# CAN_IF.net
KiCad netlist of a schematic drawn in Altium Designer
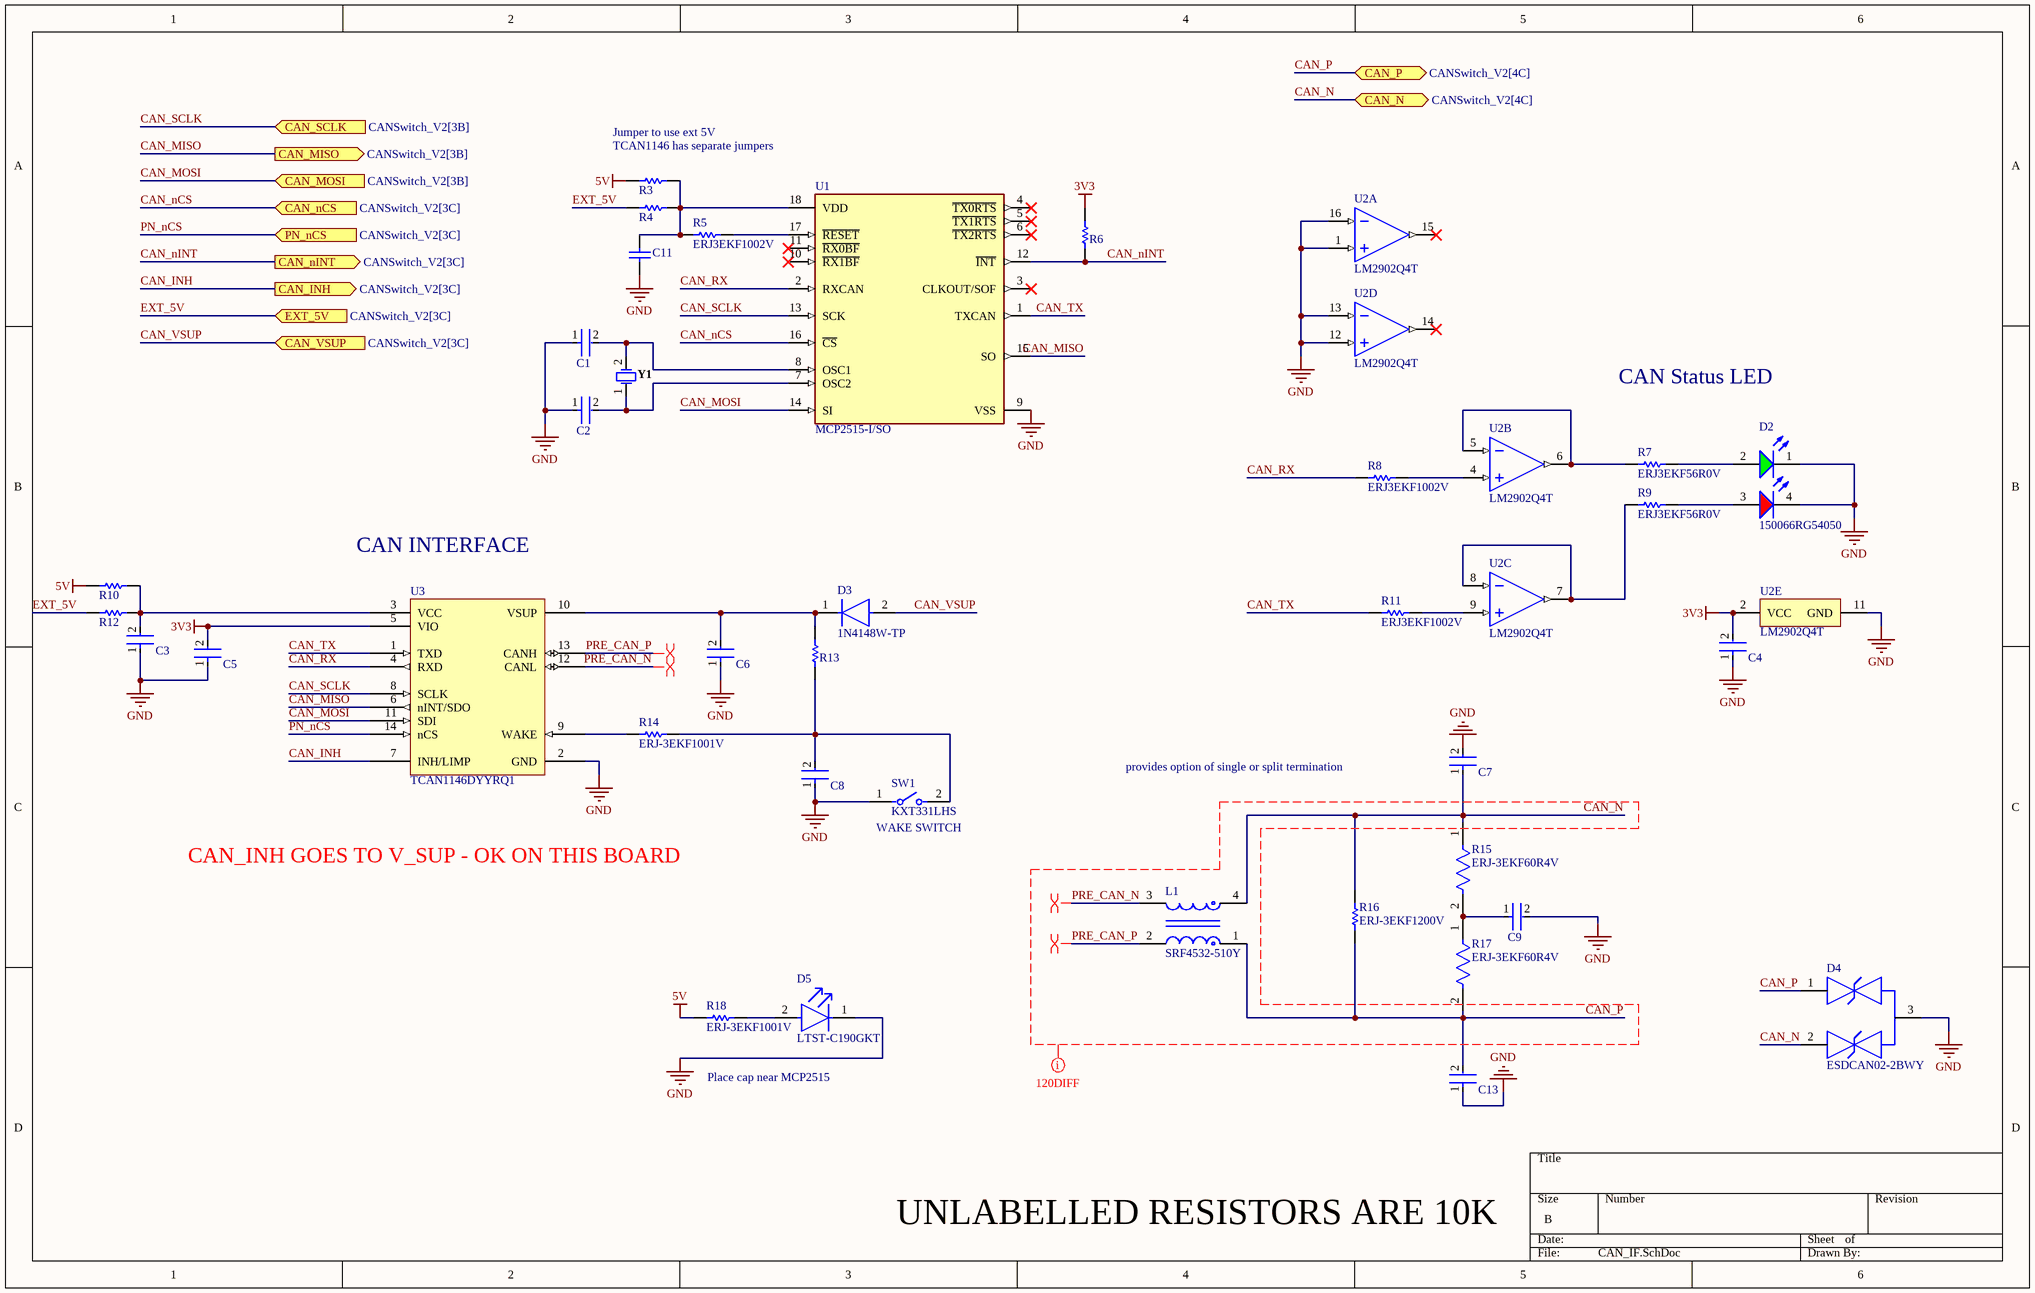
[diagram p0: CAN_IF.SchDoc]

(export (version "E")
  (design (tool "Eeschema 10.0.6"))
  (components
    (comp (ref "C1")
      (value "GRM188R60J106ME47D")
      (footprint "FP-GRM188-0_1-e0_2_0_55-IPC_A")
      (description "Chip Multilayer Ceramic Capacitors for General Purpose, 0603, 10uF, X5R, 15%, 20%, 6.3V")
      (fields (field (name "VOLTAGE") "6.3V") (field (name "TOLERANCE") "20%"))
      (libsource (lib "Altium Content Vault") (part "02cd4be3c70576c341d710602a673aa"))
    )
    (comp (ref "C2")
      (value "GRM188R60J106ME47D")
      (footprint "FP-GRM188-0_1-e0_2_0_55-IPC_A")
      (description "Chip Multilayer Ceramic Capacitors for General Purpose, 0603, 10uF, X5R, 15%, 20%, 6.3V")
      (fields (field (name "VOLTAGE") "6.3V") (field (name "TOLERANCE") "20%"))
      (libsource (lib "Altium Content Vault") (part "02cd4be3c70576c341d710602a673aa"))
    )
    (comp (ref "C3")
      (value "C0402C104K8PACTU")
      (footprint "FP-C0402-BB-MFG")
      (description "CAP CER 0.1UF 10V X5R 0402")
      (fields (field (name "MANUFACTURER") "Kemet") (field (name "TOLERANCE") "0.1"))
      (libsource (lib "Altium Content Vault") (part "b4654b650e69147ec39a6b967a45e02"))
    )
    (comp (ref "C4")
      (value "C0402C104K8PACTU")
      (footprint "FP-C0402-BB-MFG")
      (description "CAP CER 0.1UF 10V X5R 0402")
      (fields (field (name "MANUFACTURER") "Kemet") (field (name "TOLERANCE") "0.1"))
      (libsource (lib "Altium Content Vault") (part "b4654b650e69147ec39a6b967a45e02"))
    )
    (comp (ref "C5")
      (value "C0402C104K8PACTU")
      (footprint "FP-C0402-BB-MFG")
      (description "CAP CER 0.1UF 10V X5R 0402")
      (fields (field (name "MANUFACTURER") "Kemet") (field (name "TOLERANCE") "0.1"))
      (libsource (lib "Altium Content Vault") (part "b4654b650e69147ec39a6b967a45e02"))
    )
    (comp (ref "C6")
      (value "C0402C104K8PACTU")
      (footprint "FP-C0402-BB-MFG")
      (description "CAP CER 0.1UF 10V X5R 0402")
      (fields (field (name "MANUFACTURER") "Kemet") (field (name "TOLERANCE") "0.1"))
      (libsource (lib "Altium Content Vault") (part "b4654b650e69147ec39a6b967a45e02"))
    )
    (comp (ref "C7")
      (value "C0402C104K8PACTU")
      (footprint "FP-C0402-BB-MFG")
      (description "CAP CER 0.1UF 10V X5R 0402")
      (fields (field (name "MANUFACTURER") "Kemet") (field (name "TOLERANCE") "0.1"))
      (libsource (lib "Altium Content Vault") (part "b4654b650e69147ec39a6b967a45e02"))
    )
    (comp (ref "C8")
      (value "C0402C104K8PACTU")
      (footprint "FP-C0402-BB-MFG")
      (description "CAP CER 0.1UF 10V X5R 0402")
      (fields (field (name "MANUFACTURER") "Kemet") (field (name "TOLERANCE") "0.1"))
      (libsource (lib "Altium Content Vault") (part "b4654b650e69147ec39a6b967a45e02"))
    )
    (comp (ref "C9")
      (value "C0402C104K8PACTU")
      (footprint "FP-C0402-BB-MFG")
      (description "CAP CER 0.1UF 10V X5R 0402")
      (fields (field (name "MANUFACTURER") "Kemet") (field (name "TOLERANCE") "0.1"))
      (libsource (lib "Altium Content Vault") (part "b4654b650e69147ec39a6b967a45e02"))
    )
    (comp (ref "C11")
      (value "1206GC102KAT1A")
      (footprint "AVX-1206-2_L")
      (description "Chip Capacitor, 1 nF, +/- 10%, -55 to 125 degC, 1206 (3216 Metric), RoHS, Tape and Reel")
      (fields (field (name "TOLERANCE") "10%") (field (name "MANUFACTURER") "AVX"))
      (libsource (lib "Altium Content Vault") (part "CAP-NP-2"))
    )
    (comp (ref "C13")
      (value "C0402C104K8PACTU")
      (footprint "FP-C0402-BB-MFG")
      (description "CAP CER 0.1UF 10V X5R 0402")
      (fields (field (name "MANUFACTURER") "Kemet") (field (name "TOLERANCE") "0.1"))
      (libsource (lib "Altium Content Vault") (part "b4654b650e69147ec39a6b967a45e02"))
    )
    (comp (ref "D2")
      (value "150066RG54050")
      (footprint "WL-SBCD_0606")
      (description "Led, Red/Grn, 180Mcd/230Mcd, 624Nm/525Nm Rohs Compliant: Yes")
      (libsource (lib "uORocketry Hardware") (part "WL-SBCD_0606_Red & Green"))
    )
    (comp (ref "D3")
      (value "1N4148W-TP")
      (footprint "FP-SOD-123-IPC_A")
      (description "DIODE GEN PURP 100V 150MA SOD123")
      (libsource (lib "Altium Content Vault") (part "d7152d700b627762746794eb795d46e"))
    )
    (comp (ref "D4")
      (value "ESDCAN02-2BWY")
      (footprint "FP-SOT323-3L-MFG")
      (description "TVS DIODE 26.5V 44V SOT323-3")
      (fields
        (field (name "MANUFACTURER") "STMicroelectronics")
        (field (name "OCTOPART") "https://octopart.com/esdcan02-2bwy-stmicroelectronics-58631133")
      )
      (libsource (lib "Altium Content Vault") (part "0b9019fb5e52ed66df21ec1535be59d"))
    )
    (comp (ref "D5")
      (value "LTST-C190GKT")
      (footprint "FP-LTST-C190GKT-MFG")
      (description "LED GREEN CLEAR CHIP SMD")
      (fields (field (name "VOLTAGE") "2V"))
      (libsource (lib "Altium Content Vault") (part "8706943c75ba83719d021d2fdc84c58"))
    )
    (comp (ref "L1")
      (value "SRF4532-510Y")
      (footprint "FP-SRF4532-MFG")
      (description "CMC 51UH 200MA 2LN 2KOHM SMD")
      (fields (field (name "TOLERANCE") "50%"))
      (libsource (lib "Altium Content Vault") (part "aca3f6a10b859f211cca95010157f3b"))
    )
    (comp (ref "R3")
      (value "0402 JUMPER 0 OHM")
      (footprint "RESC1005X40X25NL05T05")
      (description "READ THE NAME")
      (libsource (lib "uORocketry Hardware") (part "RES"))
    )
    (comp (ref "R4")
      (value "0402 JUMPER 0 OHM")
      (footprint "RESC1005X40X25NL05T05")
      (description "READ THE NAME")
      (libsource (lib "uORocketry Hardware") (part "RES"))
    )
    (comp (ref "R5")
      (value "ERJ3EKF1002V")
      (footprint "RESC1609X55X30LL15T15")
      (description "Chip Resistor, 10 KOhm, +/- 1%, 0.1 W, -55 to 155 degC, 0603 (1608 Metric), RoHS, Tape and Reel")
      (fields (field (name "TOLERANCE") "1%") (field (name "MANUFACTURER") "Panasonic"))
      (libsource (lib "Altium Content Vault") (part "RES-2"))
    )
    (comp (ref "R6")
      (value "ERJ3EKF1002V")
      (footprint "RESC1609X55X30LL15T15")
      (description "Chip Resistor, 10 KOhm, +/- 1%, 0.1 W, -55 to 155 degC, 0603 (1608 Metric), RoHS, Tape and Reel")
      (fields (field (name "TOLERANCE") "1%") (field (name "MANUFACTURER") "Panasonic"))
      (libsource (lib "Altium Content Vault") (part "RES-2"))
    )
    (comp (ref "R7")
      (value "ERJ3EKF56R0V")
      (footprint "RESC1608X55X30NL15T15")
      (fields (field (name "MANUFACTURER") "Panasonic"))
      (libsource (lib "Altium Content Vault") (part "RES"))
    )
    (comp (ref "R8")
      (value "ERJ3EKF1002V")
      (footprint "RESC1609X55X30LL15T15")
      (description "Chip Resistor, 10 KOhm, +/- 1%, 0.1 W, -55 to 155 degC, 0603 (1608 Metric), RoHS, Tape and Reel")
      (fields (field (name "TOLERANCE") "1%") (field (name "MANUFACTURER") "Panasonic"))
      (libsource (lib "Altium Content Vault") (part "RES-2"))
    )
    (comp (ref "R9")
      (value "ERJ3EKF56R0V")
      (footprint "RESC1608X55X30NL15T15")
      (fields (field (name "MANUFACTURER") "Panasonic"))
      (libsource (lib "Altium Content Vault") (part "RES"))
    )
    (comp (ref "R10")
      (value "0402 JUMPER 0 OHM")
      (footprint "RESC1005X40X25NL05T05")
      (description "READ THE NAME")
      (libsource (lib "uORocketry Hardware") (part "RES"))
    )
    (comp (ref "R11")
      (value "ERJ3EKF1002V")
      (footprint "RESC1609X55X30LL15T15")
      (description "Chip Resistor, 10 KOhm, +/- 1%, 0.1 W, -55 to 155 degC, 0603 (1608 Metric), RoHS, Tape and Reel")
      (fields (field (name "TOLERANCE") "1%") (field (name "MANUFACTURER") "Panasonic"))
      (libsource (lib "Altium Content Vault") (part "RES-2"))
    )
    (comp (ref "R12")
      (value "0402 JUMPER 0 OHM")
      (footprint "RESC1005X40X25NL05T05")
      (description "READ THE NAME")
      (libsource (lib "uORocketry Hardware") (part "RES"))
    )
    (comp (ref "R13")
      (value "ERJ3EKF1002V")
      (footprint "RESC1609X55X30LL15T15")
      (description "Chip Resistor, 10 KOhm, +/- 1%, 0.1 W, -55 to 155 degC, 0603 (1608 Metric), RoHS, Tape and Reel")
      (fields (field (name "TOLERANCE") "1%") (field (name "MANUFACTURER") "Panasonic"))
      (libsource (lib "Altium Content Vault") (part "RES-2"))
    )
    (comp (ref "R14")
      (value "ERJ-3EKF1001V")
      (footprint "RESC1608X55X30LL15T15")
      (fields (field (name "MANUFACTURER") "Panasonic"))
      (libsource (lib "Altium Content Vault") (part "RES"))
    )
    (comp (ref "R15")
      (value "ERJ-3EKF60R4V")
      (footprint "FP-ERJ3EK-IPC_C")
      (description "RES SMD 60.4 OHM 1% 1/10W 0603")
      (fields (field (name "TOLERANCE") "1%"))
      (libsource (lib "Altium Content Vault") (part "1029c3af85768c4190bb7ad29bc67b5"))
    )
    (comp (ref "R16")
      (value "ERJ-3EKF1200V")
      (footprint "RESC1609X55X30ML15T15")
      (description "Chip Resistor, 120 Ohm, +/- 1%, 0.1 W, -55 to 155 degC, 0603 (1608 Metric), RoHS, Tape and Reel")
      (fields (field (name "TOLERANCE") "1%") (field (name "MANUFACTURER") "Panasonic"))
      (libsource (lib "Altium Content Vault") (part "RES-2"))
    )
    (comp (ref "R17")
      (value "ERJ-3EKF60R4V")
      (footprint "FP-ERJ3EK-IPC_C")
      (description "RES SMD 60.4 OHM 1% 1/10W 0603")
      (fields (field (name "TOLERANCE") "1%"))
      (libsource (lib "Altium Content Vault") (part "1029c3af85768c4190bb7ad29bc67b5"))
    )
    (comp (ref "R18")
      (value "ERJ-3EKF1001V")
      (footprint "RESC1608X55X30LL15T15")
      (fields (field (name "MANUFACTURER") "Panasonic"))
      (libsource (lib "Altium Content Vault") (part "RES"))
    )
    (comp (ref "SW1")
      (value "KXT331LHS")
      (footprint "FP-KXT331LHS-MFG")
      (description "SWITCH TACTILE SPST-NO 0.02A 15V")
      (libsource (lib "Altium Content Vault") (part "bb27bde45df87f1f469753f287ef5ae"))
    )
    (comp (ref "U1")
      (value "MCP2515-I/SO")
      (footprint "FP-C04-051-MFG")
      (description "IC CAN CONTROLLER W/SPI 18SOIC")
      (fields
        (field (name "MANUFACTURER") "Microchip")
        (field (name "OCTOPART") "https://octopart.com/mcp2515-i%2Fso-microchip-430187")
      )
      (libsource (lib "Altium Content Vault") (part "1c78ea6ff576bac94664e2637e1b479"))
    )
    (comp (ref "U2")
      (value "LM2902Q4T")
      (footprint "LM2902Q4T-Footprint-1")
      (description "LM2902 Series 30 V 1.3 MHz Low-Power Quad Operational Amplifier - QFN-16 (3x3)")
      (libsource (lib "uORocketry Hardware") (part "LM2902Q4T"))
    )
    (comp (ref "U3")
      (value "TCAN1146DYYRQ1")
      (footprint "TCAN1146DYYRQ1-Footprint-1")
      (libsource (lib "uORocketry Hardware") (part "TCAN1146DYYRQ1"))
    )
    (comp (ref "Y1")
      (value "FOXSLF/160-20")
      (footprint "FOX-FOXSLF160-20")
      (description "Resistance Weld Thru-Hole Crystal, 16 MHz, -20 to 70 degC, 2-Pin THD, RoHS, Bulk")
      (fields (field (name "TOLERANCE") "1%"))
      (libsource (lib "Altium Content Vault") (part "XTAL-1-2-2"))
    )
  )
  (nets
    (net (code "1") (name "/CAN_INH") (class "Default")
      (node (ref "U3") (pin "7") (pinfunction "INH/LIMP_7") (pintype "passive"))
    )
    (net (code "2") (name "/CAN_MISO") (class "Default")
      (node (ref "U1") (pin "15") (pinfunction "SO_15") (pintype "output"))
      (node (ref "U3") (pin "6") (pinfunction "nINT/SDO_6") (pintype "output"))
    )
    (net (code "3") (name "/CAN_MOSI") (class "Default")
      (node (ref "U1") (pin "14") (pinfunction "SI_14") (pintype "input"))
      (node (ref "U3") (pin "11") (pinfunction "SDI_11") (pintype "input"))
    )
    (net (code "4") (name "/CAN_N") (class "Default")
      (node (ref "C7") (pin "1") (pinfunction "1_1") (pintype "passive"))
      (node (ref "D4") (pin "2") (pinfunction "2_2") (pintype "passive"))
      (node (ref "L1") (pin "4") (pinfunction "4_4") (pintype "passive"))
      (node (ref "R15") (pin "1") (pinfunction "1_1") (pintype "passive"))
      (node (ref "R16") (pin "1") (pinfunction "1_1") (pintype "passive"))
    )
    (net (code "5") (name "/CAN_P") (class "Default")
      (node (ref "C13") (pin "2") (pinfunction "2_2") (pintype "passive"))
      (node (ref "D4") (pin "1") (pinfunction "1_1") (pintype "passive"))
      (node (ref "L1") (pin "1") (pinfunction "1_1") (pintype "passive"))
      (node (ref "R16") (pin "2") (pinfunction "2_2") (pintype "passive"))
      (node (ref "R17") (pin "2") (pinfunction "2_2") (pintype "passive"))
    )
    (net (code "6") (name "/CAN_RX") (class "Default")
      (node (ref "R8") (pin "1") (pinfunction "1_1") (pintype "passive"))
      (node (ref "U1") (pin "2") (pinfunction "RXCAN_2") (pintype "input"))
      (node (ref "U3") (pin "4") (pinfunction "RXD_4") (pintype "output"))
    )
    (net (code "7") (name "/CAN_SCLK") (class "Default")
      (node (ref "U1") (pin "13") (pinfunction "SCK_13") (pintype "input"))
      (node (ref "U3") (pin "8") (pinfunction "SCLK_8") (pintype "input"))
    )
    (net (code "8") (name "/CAN_TX") (class "Default")
      (node (ref "R11") (pin "2") (pinfunction "2_2") (pintype "passive"))
      (node (ref "U1") (pin "1") (pinfunction "TXCAN_1") (pintype "output"))
      (node (ref "U3") (pin "1") (pinfunction "TXD_1") (pintype "input"))
    )
    (net (code "9") (name "/CAN_VSUP") (class "Default")
      (node (ref "D3") (pin "2") (pinfunction "A_2") (pintype "passive"))
    )
    (net (code "10") (name "/CAN_nCS") (class "Default")
      (node (ref "U1") (pin "16") (pinfunction "~{CS}_16") (pintype "input"))
    )
    (net (code "11") (name "/CAN_nINT") (class "Default")
      (node (ref "R6") (pin "2") (pinfunction "2_2") (pintype "passive"))
      (node (ref "U1") (pin "12") (pinfunction "~{INT}_12") (pintype "output"))
    )
    (net (code "12") (name "/EXT_5V") (class "Default")
      (node (ref "R12") (pin "1") (pinfunction "1_1") (pintype "passive"))
      (node (ref "R4") (pin "1") (pinfunction "1_1") (pintype "passive"))
    )
    (net (code "13") (name "/PN_nCS") (class "Default")
      (node (ref "U3") (pin "14") (pinfunction "nCS_14") (pintype "input"))
    )
    (net (code "14") (name "/PRE_CAN_N") (class "Default")
      (node (ref "L1") (pin "3") (pinfunction "3_3") (pintype "passive"))
      (node (ref "U3") (pin "12") (pinfunction "CANL_12") (pintype "bidirectional"))
    )
    (net (code "15") (name "/PRE_CAN_P") (class "Default")
      (node (ref "L1") (pin "2") (pinfunction "2_2") (pintype "passive"))
      (node (ref "U3") (pin "13") (pinfunction "CANH_13") (pintype "bidirectional"))
    )
    (net (code "16") (name "3V3") (class "Default")
      (node (ref "C4") (pin "2") (pinfunction "2_2") (pintype "passive"))
      (node (ref "C5") (pin "2") (pinfunction "2_2") (pintype "passive"))
      (node (ref "R6") (pin "1") (pinfunction "1_1") (pintype "passive"))
      (node (ref "U2") (pin "2") (pinfunction "VCC_2") (pintype "power_in"))
      (node (ref "U3") (pin "5") (pinfunction "VIO_5") (pintype "power_in"))
    )
    (net (code "17") (name "5V") (class "Default")
      (node (ref "R10") (pin "1") (pinfunction "1_1") (pintype "passive"))
      (node (ref "R18") (pin "2") (pinfunction "2_2") (pintype "passive"))
      (node (ref "R3") (pin "1") (pinfunction "1_1") (pintype "passive"))
    )
    (net (code "18") (name "GND") (class "Default")
      (node (ref "C1") (pin "1") (pinfunction "1_1") (pintype "passive"))
      (node (ref "C11") (pin "1") (pinfunction "1_1") (pintype "passive"))
      (node (ref "C13") (pin "1") (pinfunction "1_1") (pintype "passive"))
      (node (ref "C2") (pin "1") (pinfunction "1_1") (pintype "passive"))
      (node (ref "C3") (pin "1") (pinfunction "1_1") (pintype "passive"))
      (node (ref "C4") (pin "1") (pinfunction "1_1") (pintype "passive"))
      (node (ref "C5") (pin "1") (pinfunction "1_1") (pintype "passive"))
      (node (ref "C6") (pin "1") (pinfunction "1_1") (pintype "passive"))
      (node (ref "C7") (pin "2") (pinfunction "2_2") (pintype "passive"))
      (node (ref "C8") (pin "1") (pinfunction "1_1") (pintype "passive"))
      (node (ref "C9") (pin "2") (pinfunction "2_2") (pintype "passive"))
      (node (ref "D2") (pin "1") (pinfunction "K_1") (pintype "passive"))
      (node (ref "D2") (pin "4") (pinfunction "K_4") (pintype "passive"))
      (node (ref "D4") (pin "3") (pinfunction "3_3") (pintype "passive"))
      (node (ref "D5") (pin "1") (pinfunction "C_1") (pintype "passive"))
      (node (ref "SW1") (pin "1") (pinfunction "1_1") (pintype "passive"))
      (node (ref "U1") (pin "9") (pinfunction "VSS_9") (pintype "power_in"))
      (node (ref "U2") (pin "1") (pinfunction "1IN+_1") (pintype "input"))
      (node (ref "U2") (pin "11") (pinfunction "GND_11") (pintype "power_in"))
      (node (ref "U2") (pin "12") (pinfunction "4IN+_12") (pintype "input"))
      (node (ref "U2") (pin "13") (pinfunction "4IN-_13") (pintype "input"))
      (node (ref "U2") (pin "16") (pinfunction "1IN-_16") (pintype "input"))
      (node (ref "U3") (pin "2") (pinfunction "GND_2") (pintype "power_in"))
    )
    (net (code "19") (name "Net-(C8-Pad2)") (class "Default")
      (node (ref "C8") (pin "2") (pinfunction "2_2") (pintype "passive"))
      (node (ref "R13") (pin "2") (pinfunction "2_2") (pintype "passive"))
      (node (ref "R14") (pin "2") (pinfunction "2_2") (pintype "passive"))
      (node (ref "SW1") (pin "2") (pinfunction "2_2") (pintype "passive"))
    )
    (net (code "20") (name "Net-(C9-Pad1)") (class "Default")
      (node (ref "C9") (pin "1") (pinfunction "1_1") (pintype "passive"))
      (node (ref "R15") (pin "2") (pinfunction "2_2") (pintype "passive"))
      (node (ref "R17") (pin "1") (pinfunction "1_1") (pintype "passive"))
    )
    (net (code "21") (name "Net-(D2-A-Pad2)") (class "Default")
      (node (ref "D2") (pin "2") (pinfunction "A_2") (pintype "passive"))
      (node (ref "R7") (pin "1") (pinfunction "1_1") (pintype "passive"))
    )
    (net (code "22") (name "Net-(D2-A-Pad3)") (class "Default")
      (node (ref "D2") (pin "3") (pinfunction "A_3") (pintype "passive"))
      (node (ref "R9") (pin "1") (pinfunction "1_1") (pintype "passive"))
    )
    (net (code "23") (name "Net-(D3-C)") (class "Default")
      (node (ref "C6") (pin "2") (pinfunction "2_2") (pintype "passive"))
      (node (ref "D3") (pin "1") (pinfunction "C_1") (pintype "passive"))
      (node (ref "R13") (pin "1") (pinfunction "1_1") (pintype "passive"))
      (node (ref "U3") (pin "10") (pinfunction "VSUP_10") (pintype "power_in"))
    )
    (net (code "24") (name "Net-(D5-A)") (class "Default")
      (node (ref "D5") (pin "2") (pinfunction "A_2") (pintype "passive"))
      (node (ref "R18") (pin "1") (pinfunction "1_1") (pintype "passive"))
    )
    (net (code "25") (name "Net-(U1-OSC1)") (class "Default")
      (node (ref "C1") (pin "2") (pinfunction "2_2") (pintype "passive"))
      (node (ref "U1") (pin "8") (pinfunction "OSC1_8") (pintype "input"))
      (node (ref "Y1") (pin "2") (pinfunction "2_2") (pintype "passive"))
    )
    (net (code "26") (name "Net-(U1-OSC2)") (class "Default")
      (node (ref "C2") (pin "2") (pinfunction "2_2") (pintype "passive"))
      (node (ref "U1") (pin "7") (pinfunction "OSC2_7") (pintype "input"))
      (node (ref "Y1") (pin "1") (pinfunction "1_1") (pintype "passive"))
    )
    (net (code "27") (name "Net-(U1-VDD)") (class "Default")
      (node (ref "C11") (pin "2") (pinfunction "2_2") (pintype "passive"))
      (node (ref "R3") (pin "2") (pinfunction "2_2") (pintype "passive"))
      (node (ref "R4") (pin "2") (pinfunction "2_2") (pintype "passive"))
      (node (ref "R5") (pin "1") (pinfunction "1_1") (pintype "passive"))
      (node (ref "U1") (pin "18") (pinfunction "VDD_18") (pintype "power_in"))
    )
    (net (code "28") (name "Net-(U1-~{RESET})") (class "Default")
      (node (ref "R5") (pin "2") (pinfunction "2_2") (pintype "passive"))
      (node (ref "U1") (pin "17") (pinfunction "~{RESET}_17") (pintype "input"))
    )
    (net (code "29") (name "Net-(U2B-2IN+)") (class "Default")
      (node (ref "R8") (pin "2") (pinfunction "2_2") (pintype "passive"))
      (node (ref "U2") (pin "4") (pinfunction "2IN+_4") (pintype "input"))
    )
    (net (code "30") (name "Net-(U2B-2IN-)") (class "Default")
      (node (ref "R7") (pin "2") (pinfunction "2_2") (pintype "passive"))
      (node (ref "U2") (pin "5") (pinfunction "2IN-_5") (pintype "input"))
      (node (ref "U2") (pin "6") (pinfunction "2OUT_6") (pintype "output"))
    )
    (net (code "31") (name "Net-(U2C-3IN+)") (class "Default")
      (node (ref "R11") (pin "1") (pinfunction "1_1") (pintype "passive"))
      (node (ref "U2") (pin "9") (pinfunction "3IN+_9") (pintype "input"))
    )
    (net (code "32") (name "Net-(U2C-3IN-)") (class "Default")
      (node (ref "R9") (pin "2") (pinfunction "2_2") (pintype "passive"))
      (node (ref "U2") (pin "7") (pinfunction "3OUT_7") (pintype "output"))
      (node (ref "U2") (pin "8") (pinfunction "3IN-_8") (pintype "input"))
    )
    (net (code "33") (name "Net-(U3-VCC)") (class "Default")
      (node (ref "C3") (pin "2") (pinfunction "2_2") (pintype "passive"))
      (node (ref "R10") (pin "2") (pinfunction "2_2") (pintype "passive"))
      (node (ref "R12") (pin "2") (pinfunction "2_2") (pintype "passive"))
      (node (ref "U3") (pin "3") (pinfunction "VCC_3") (pintype "power_in"))
    )
    (net (code "34") (name "Net-(U3-WAKE)") (class "Default")
      (node (ref "R14") (pin "1") (pinfunction "1_1") (pintype "passive"))
      (node (ref "U3") (pin "9") (pinfunction "WAKE_9") (pintype "input"))
    )
    (net (code "35") (name "unconnected-(U1-CLKOUT{slash}SOF-Pad3)") (class "Default")
      (node (ref "U1") (pin "3") (pinfunction "CLKOUT/SOF_3") (pintype "output+no_connect"))
    )
    (net (code "36") (name "unconnected-(U1-~{RX0BF}-Pad11)") (class "Default")
      (node (ref "U1") (pin "11") (pinfunction "~{RX0BF}_11") (pintype "input+no_connect"))
    )
    (net (code "37") (name "unconnected-(U1-~{RX1BF}-Pad10)") (class "Default")
      (node (ref "U1") (pin "10") (pinfunction "~{RX1BF}_10") (pintype "input+no_connect"))
    )
    (net (code "38") (name "unconnected-(U1-~{TX0RTS}-Pad4)") (class "Default")
      (node (ref "U1") (pin "4") (pinfunction "~{TX0RTS}_4") (pintype "output+no_connect"))
    )
    (net (code "39") (name "unconnected-(U1-~{TX1RTS}-Pad5)") (class "Default")
      (node (ref "U1") (pin "5") (pinfunction "~{TX1RTS}_5") (pintype "output+no_connect"))
    )
    (net (code "40") (name "unconnected-(U1-~{TX2RTS}-Pad6)") (class "Default")
      (node (ref "U1") (pin "6") (pinfunction "~{TX2RTS}_6") (pintype "output+no_connect"))
    )
    (net (code "41") (name "unconnected-(U2A-1OUT-Pad15)") (class "Default")
      (node (ref "U2") (pin "15") (pinfunction "1OUT_15") (pintype "output+no_connect"))
    )
    (net (code "42") (name "unconnected-(U2D-4OUT-Pad14)") (class "Default")
      (node (ref "U2") (pin "14") (pinfunction "4OUT_14") (pintype "output+no_connect"))
    )
  )
)
